# synthesizer-IF-Si4112-v1.net
KiCad netlist of a schematic drawn in EAGLE
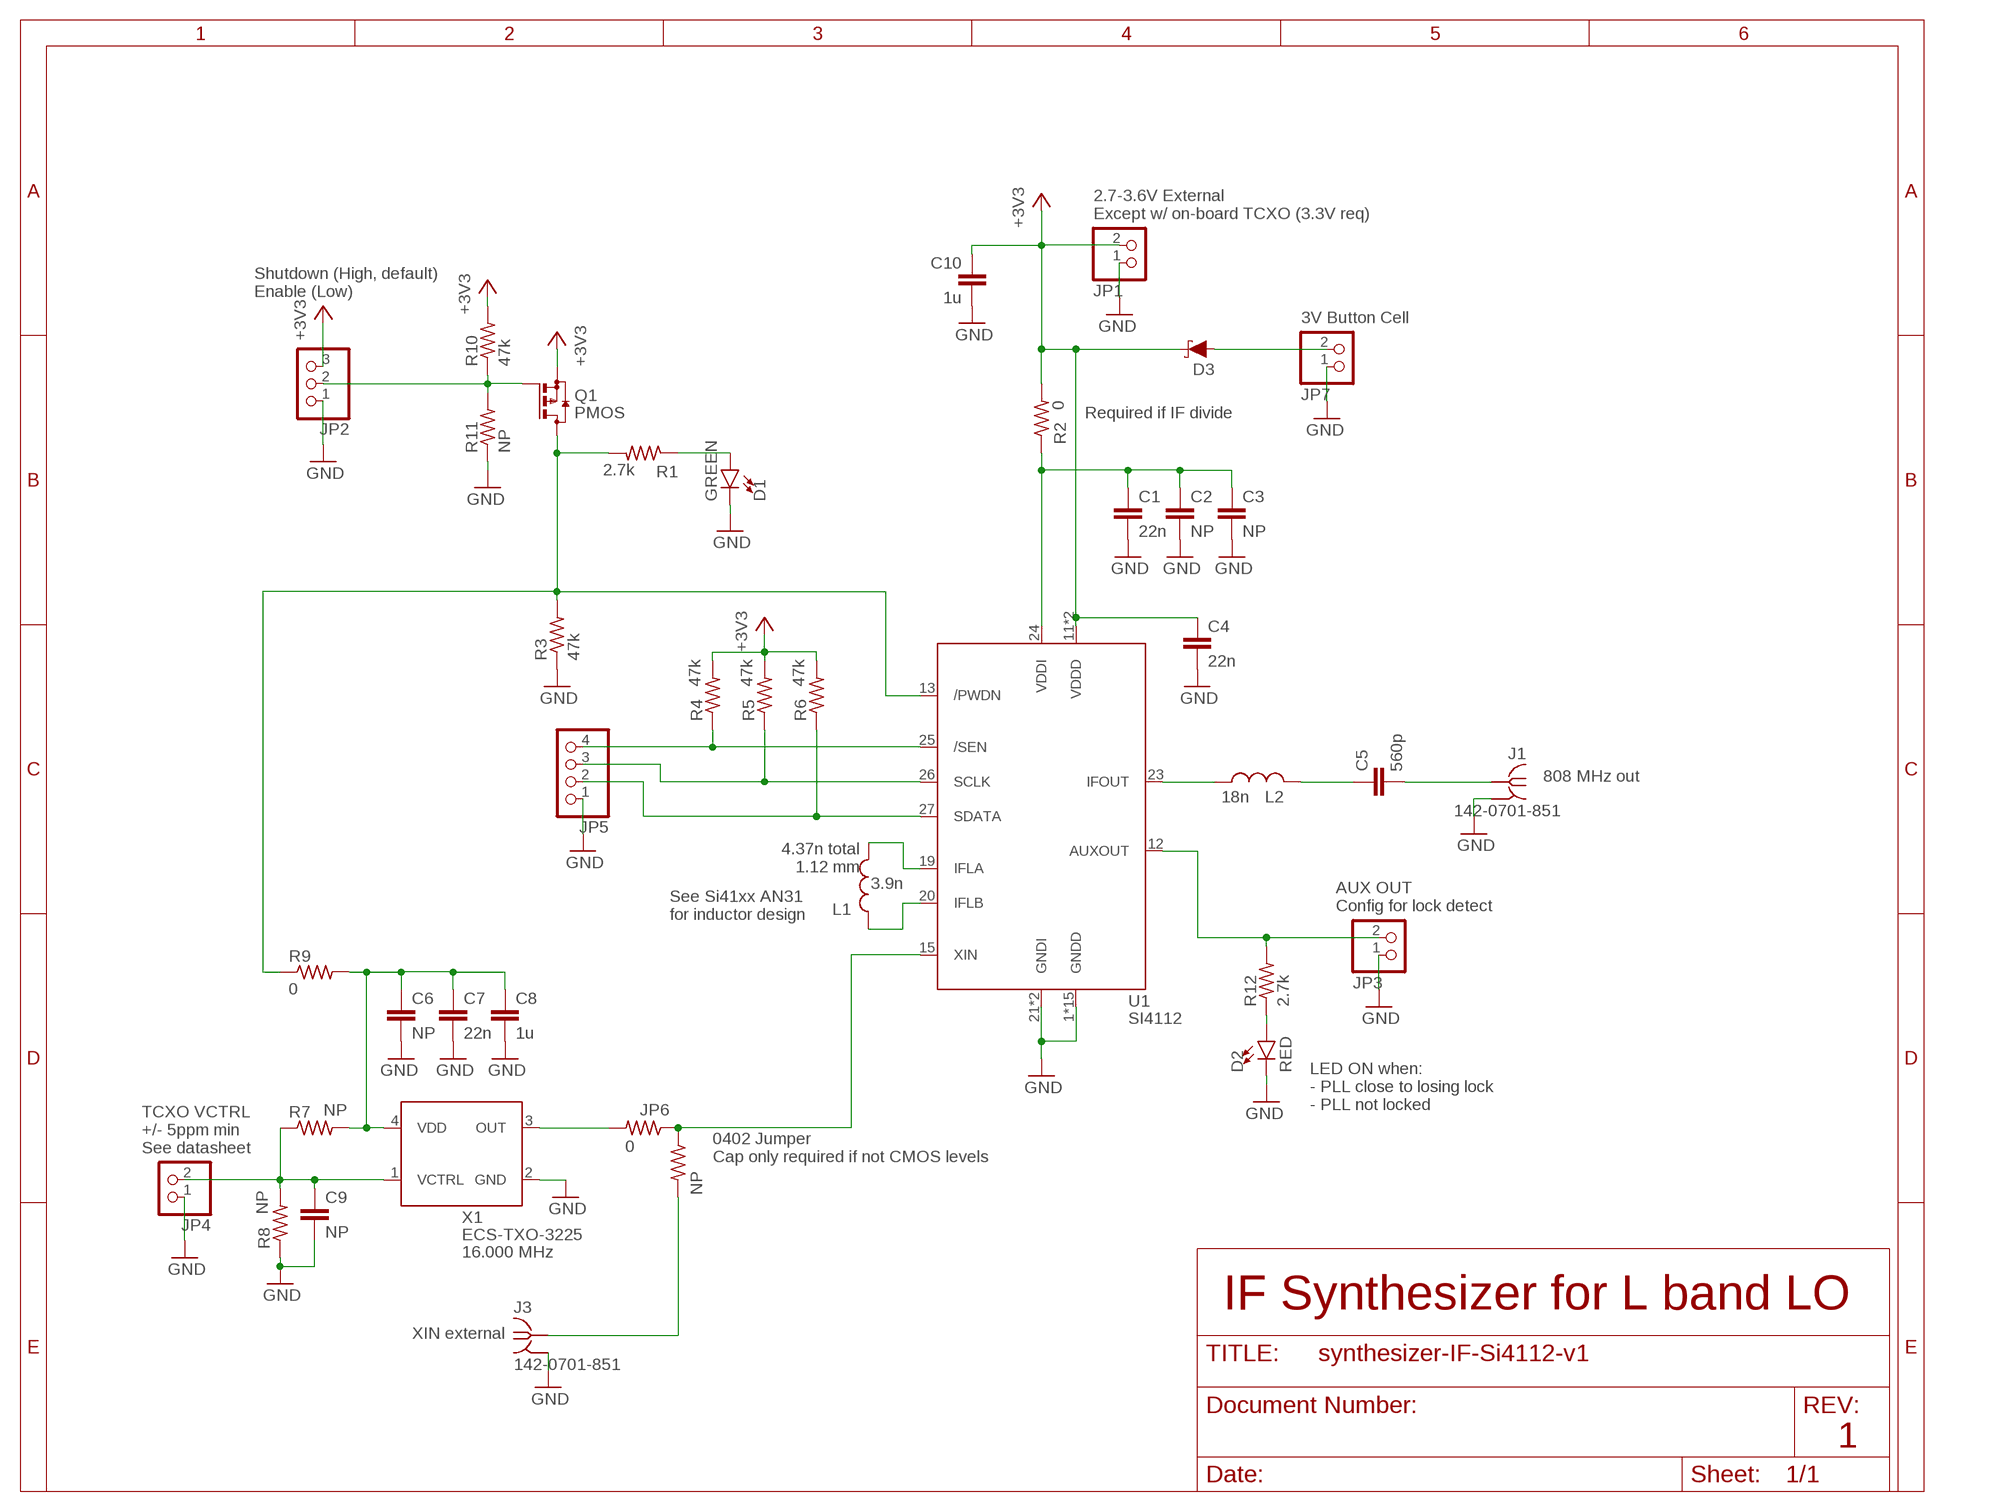
[diagram p0: schematic, sheet 1]

(export (version "E")
  (design (tool "Eeschema 10.0.6"))
  (components
    (comp (ref "C1")
      (value "22n")
      (footprint "eagle-import:.0603-B-NOSILK")
      (libsource (lib "eagle-import") (part "C-EU0603-B-NOSILK"))
    )
    (comp (ref "C2")
      (value "NP")
      (footprint "eagle-import:.0603-B-NOSILK")
      (libsource (lib "eagle-import") (part "C-EU0603-B-NOSILK"))
    )
    (comp (ref "C3")
      (value "NP")
      (footprint "eagle-import:.0603-B-NOSILK")
      (libsource (lib "eagle-import") (part "C-EU0603-B-NOSILK"))
    )
    (comp (ref "C4")
      (value "22n")
      (footprint "eagle-import:.0603-B-NOSILK")
      (libsource (lib "eagle-import") (part "C-EU0603-B-NOSILK"))
    )
    (comp (ref "C5")
      (value "560p")
      (footprint "eagle-import:.0402-B-NOSILK")
      (libsource (lib "eagle-import") (part "C-EU0402-B-NOSILK"))
    )
    (comp (ref "C6")
      (value "NP")
      (footprint "eagle-import:.0603-B-NOSILK")
      (libsource (lib "eagle-import") (part "C-EU0603-B-NOSILK"))
    )
    (comp (ref "C7")
      (value "22n")
      (footprint "eagle-import:.0603-B-NOSILK")
      (libsource (lib "eagle-import") (part "C-EU0603-B-NOSILK"))
    )
    (comp (ref "C8")
      (value "1u")
      (footprint "eagle-import:.0603-B-NOSILK")
      (libsource (lib "eagle-import") (part "C-EU0603-B-NOSILK"))
    )
    (comp (ref "C9")
      (value "NP")
      (footprint "eagle-import:.0603-B-NOSILK")
      (libsource (lib "eagle-import") (part "C-EU0603-B-NOSILK"))
    )
    (comp (ref "C10")
      (value "1u")
      (footprint "eagle-import:.0603-B-NOSILK")
      (libsource (lib "eagle-import") (part "C-EU0603-B-NOSILK"))
    )
    (comp (ref "D1")
      (value "GREEN")
      (footprint "eagle-import:LED-0603")
      (libsource (lib "eagle-import") (part "LED-GREEN0603"))
    )
    (comp (ref "D2")
      (value "RED")
      (footprint "eagle-import:LED-0603")
      (libsource (lib "eagle-import") (part "LED-GREEN0603"))
    )
    (comp (ref "D3")
      (value "120mA/40V/370mV")
      (footprint "eagle-import:SOD-523")
      (libsource (lib "eagle-import") (part "DIODE-SCHOTTKY-RB751S40"))
    )
    (comp (ref "J1")
      (value "142-0701-851")
      (footprint "eagle-import:142-0701-851")
      (libsource (lib "eagle-import") (part "142-0701-851"))
    )
    (comp (ref "J3")
      (value "142-0701-851")
      (footprint "eagle-import:142-0701-851")
      (libsource (lib "eagle-import") (part "142-0701-851"))
    )
    (comp (ref "JP1")
      (value "PINHD-1X2")
      (footprint "eagle-import:1X02")
      (libsource (lib "eagle-import") (part "PINHD-1X2"))
    )
    (comp (ref "JP2")
      (value "PINHD-1X3")
      (footprint "eagle-import:1X03")
      (libsource (lib "eagle-import") (part "PINHD-1X3"))
    )
    (comp (ref "JP3")
      (value "PINHD-1X2")
      (footprint "eagle-import:1X02")
      (libsource (lib "eagle-import") (part "PINHD-1X2"))
    )
    (comp (ref "JP4")
      (value "PINHD-1X2")
      (footprint "eagle-import:1X02")
      (libsource (lib "eagle-import") (part "PINHD-1X2"))
    )
    (comp (ref "JP5")
      (value "PINHD-1X4")
      (footprint "eagle-import:1X04")
      (libsource (lib "eagle-import") (part "PINHD-1X4"))
    )
    (comp (ref "JP6")
      (value "0")
      (footprint "eagle-import:.0402-B-NOSILK")
      (libsource (lib "eagle-import") (part "R-US_0402-B-NOSILK"))
    )
    (comp (ref "JP7")
      (value "PINHD-1X2")
      (footprint "eagle-import:1X02")
      (libsource (lib "eagle-import") (part "PINHD-1X2"))
    )
    (comp (ref "L1")
      (value "3.9n")
      (footprint "eagle-import:.0402-C-NOSILK")
      (libsource (lib "eagle-import") (part "L-US0402-C-NOSILK"))
    )
    (comp (ref "L2")
      (value "18n")
      (footprint "eagle-import:.0402-B-NOSILK")
      (libsource (lib "eagle-import") (part "L-US0402-B-NOSILK"))
    )
    (comp (ref "Q1")
      (value "PMOS")
      (footprint "eagle-import:SOT23")
      (libsource (lib "eagle-import") (part "BSS84"))
    )
    (comp (ref "R1")
      (value "2.7k")
      (footprint "eagle-import:.0603-B-NOSILK")
      (libsource (lib "eagle-import") (part "R-US_0603-B-NOSILK"))
    )
    (comp (ref "R2")
      (value "0")
      (footprint "eagle-import:.0603-B-NOSILK")
      (libsource (lib "eagle-import") (part "R-US_0603-B-NOSILK"))
    )
    (comp (ref "R3")
      (value "47k")
      (footprint "eagle-import:.0402-B-NOSILK")
      (libsource (lib "eagle-import") (part "R-US_0402-B-NOSILK"))
    )
    (comp (ref "R4")
      (value "47k")
      (footprint "eagle-import:.0402-B-NOSILK")
      (libsource (lib "eagle-import") (part "R-US_0402-B-NOSILK"))
    )
    (comp (ref "R5")
      (value "47k")
      (footprint "eagle-import:.0402-B-NOSILK")
      (libsource (lib "eagle-import") (part "R-US_0402-B-NOSILK"))
    )
    (comp (ref "R6")
      (value "47k")
      (footprint "eagle-import:.0402-B-NOSILK")
      (libsource (lib "eagle-import") (part "R-US_0402-B-NOSILK"))
    )
    (comp (ref "R7")
      (value "NP")
      (footprint "eagle-import:.0603-B-NOSILK")
      (libsource (lib "eagle-import") (part "R-US_0603-B-NOSILK"))
    )
    (comp (ref "R8")
      (value "NP")
      (footprint "eagle-import:.0603-B-NOSILK")
      (libsource (lib "eagle-import") (part "R-US_0603-B-NOSILK"))
    )
    (comp (ref "R9")
      (value "0")
      (footprint "eagle-import:.0603-B-NOSILK")
      (libsource (lib "eagle-import") (part "R-US_0603-B-NOSILK"))
    )
    (comp (ref "R10")
      (value "47k")
      (footprint "eagle-import:.0402-B-NOSILK")
      (libsource (lib "eagle-import") (part "R-US_0402-B-NOSILK"))
    )
    (comp (ref "R11")
      (value "NP")
      (footprint "eagle-import:.0402-B-NOSILK")
      (libsource (lib "eagle-import") (part "R-US_0402-B-NOSILK"))
    )
    (comp (ref "R12")
      (value "2.7k")
      (footprint "eagle-import:.0603-B-NOSILK")
      (libsource (lib "eagle-import") (part "R-US_0603-B-NOSILK"))
    )
    (comp (ref "R99")
      (value "NP")
      (footprint "eagle-import:.0402-B-NOSILK")
      (libsource (lib "eagle-import") (part "R-US_0402-B-NOSILK"))
    )
    (comp (ref "U1")
      (value "SI4112")
      (footprint "eagle-import:QFN28-5X5-WITH-CENTER-PAD")
      (libsource (lib "eagle-import") (part "SI4112"))
    )
    (comp (ref "X1")
      (value "ECS-TXO-3225")
      (footprint "eagle-import:3.2X2.5")
      (libsource (lib "eagle-import") (part "ECS-TXO-3225"))
    )
  )
  (nets
    (net (code "1") (name "+3V3") (class "Default")
      (node (ref "C10") (pin "1") (pinfunction "1_1") (pintype "passive"))
      (node (ref "C4") (pin "1") (pinfunction "1_1") (pintype "passive"))
      (node (ref "D3") (pin "C") (pinfunction "C_C") (pintype "passive"))
      (node (ref "JP1") (pin "2") (pinfunction "2_2") (pintype "passive"))
      (node (ref "JP2") (pin "3") (pinfunction "3_3") (pintype "passive"))
      (node (ref "Q1") (pin "2") (pinfunction "S_2") (pintype "passive"))
      (node (ref "R10") (pin "2") (pinfunction "2_2") (pintype "passive"))
      (node (ref "R2") (pin "2") (pinfunction "2_2") (pintype "passive"))
      (node (ref "R4") (pin "2") (pinfunction "2_2") (pintype "passive"))
      (node (ref "R5") (pin "2") (pinfunction "2_2") (pintype "passive"))
      (node (ref "R6") (pin "2") (pinfunction "2_2") (pintype "passive"))
      (node (ref "U1") (pin "11") (pinfunction "VDDD_11") (pintype "power_in"))
      (node (ref "U1") (pin "17") (pinfunction "VDDD_17") (pintype "power_in"))
    )
    (net (code "2") (name "GND") (class "Default")
      (node (ref "C1") (pin "2") (pinfunction "2_2") (pintype "passive"))
      (node (ref "C10") (pin "2") (pinfunction "2_2") (pintype "passive"))
      (node (ref "C2") (pin "2") (pinfunction "2_2") (pintype "passive"))
      (node (ref "C3") (pin "2") (pinfunction "2_2") (pintype "passive"))
      (node (ref "C4") (pin "2") (pinfunction "2_2") (pintype "passive"))
      (node (ref "C6") (pin "2") (pinfunction "2_2") (pintype "passive"))
      (node (ref "C7") (pin "2") (pinfunction "2_2") (pintype "passive"))
      (node (ref "C8") (pin "2") (pinfunction "2_2") (pintype "passive"))
      (node (ref "C9") (pin "2") (pinfunction "2_2") (pintype "passive"))
      (node (ref "D1") (pin "C") (pinfunction "C_C") (pintype "passive"))
      (node (ref "D2") (pin "C") (pinfunction "C_C") (pintype "passive"))
      (node (ref "J1") (pin "GND1") (pinfunction "GND_GND1") (pintype "bidirectional"))
      (node (ref "J1") (pin "GND2") (pinfunction "GND_GND2") (pintype "bidirectional"))
      (node (ref "J1") (pin "GND3") (pinfunction "GND_GND3") (pintype "bidirectional"))
      (node (ref "J1") (pin "GND4") (pinfunction "GND_GND4") (pintype "bidirectional"))
      (node (ref "J3") (pin "GND1") (pinfunction "GND_GND1") (pintype "bidirectional"))
      (node (ref "J3") (pin "GND2") (pinfunction "GND_GND2") (pintype "bidirectional"))
      (node (ref "J3") (pin "GND3") (pinfunction "GND_GND3") (pintype "bidirectional"))
      (node (ref "J3") (pin "GND4") (pinfunction "GND_GND4") (pintype "bidirectional"))
      (node (ref "JP1") (pin "1") (pinfunction "1_1") (pintype "passive"))
      (node (ref "JP2") (pin "1") (pinfunction "1_1") (pintype "passive"))
      (node (ref "JP3") (pin "1") (pinfunction "1_1") (pintype "passive"))
      (node (ref "JP4") (pin "1") (pinfunction "1_1") (pintype "passive"))
      (node (ref "JP5") (pin "1") (pinfunction "1_1") (pintype "passive"))
      (node (ref "JP7") (pin "1") (pinfunction "1_1") (pintype "passive"))
      (node (ref "R11") (pin "1") (pinfunction "1_1") (pintype "passive"))
      (node (ref "R3") (pin "1") (pinfunction "1_1") (pintype "passive"))
      (node (ref "R8") (pin "1") (pinfunction "1_1") (pintype "passive"))
      (node (ref "U1") (pin "1") (pinfunction "GNDD_1") (pintype "power_in"))
      (node (ref "U1") (pin "10") (pinfunction "GNDD_10") (pintype "power_in"))
      (node (ref "U1") (pin "14") (pinfunction "GNDD_14") (pintype "power_in"))
      (node (ref "U1") (pin "16") (pinfunction "GNDD_16") (pintype "power_in"))
      (node (ref "U1") (pin "18") (pinfunction "GNDD_18") (pintype "power_in"))
      (node (ref "U1") (pin "2") (pinfunction "GNDD_2") (pintype "power_in"))
      (node (ref "U1") (pin "21") (pinfunction "GNDI_21") (pintype "power_in"))
      (node (ref "U1") (pin "22") (pinfunction "GNDI_22") (pintype "power_in"))
      (node (ref "U1") (pin "28") (pinfunction "GNDD_28") (pintype "power_in"))
      (node (ref "U1") (pin "3") (pinfunction "GNDD_3") (pintype "power_in"))
      (node (ref "U1") (pin "4") (pinfunction "GNDD_4") (pintype "power_in"))
      (node (ref "U1") (pin "5") (pinfunction "GNDD_5") (pintype "power_in"))
      (node (ref "U1") (pin "6") (pinfunction "GNDD_6") (pintype "power_in"))
      (node (ref "U1") (pin "7") (pinfunction "GNDD_7") (pintype "power_in"))
      (node (ref "U1") (pin "8") (pinfunction "GNDD_8") (pintype "power_in"))
      (node (ref "U1") (pin "9") (pinfunction "GNDD_9") (pintype "power_in"))
      (node (ref "U1") (pin "PAD") (pinfunction "GNDD_PAD") (pintype "power_in"))
      (node (ref "X1") (pin "2") (pinfunction "GND_2") (pintype "power_in"))
    )
    (net (code "3") (name "Net-(C5-Pad1)") (class "Default")
      (node (ref "C5") (pin "1") (pinfunction "1_1") (pintype "passive"))
      (node (ref "L2") (pin "2") (pinfunction "2_2") (pintype "passive"))
    )
    (net (code "4") (name "Net-(D1-PadA)") (class "Default")
      (node (ref "D1") (pin "A") (pinfunction "A_A") (pintype "passive"))
      (node (ref "R1") (pin "1") (pinfunction "1_1") (pintype "passive"))
    )
    (net (code "5") (name "Net-(D2-PadA)") (class "Default")
      (node (ref "D2") (pin "A") (pinfunction "A_A") (pintype "passive"))
      (node (ref "R12") (pin "1") (pinfunction "1_1") (pintype "passive"))
    )
    (net (code "6") (name "Net-(D3-PadA)") (class "Default")
      (node (ref "D3") (pin "A") (pinfunction "A_A") (pintype "passive"))
      (node (ref "JP7") (pin "2") (pinfunction "2_2") (pintype "passive"))
    )
    (net (code "7") (name "Net-(J1-RF)") (class "Default")
      (node (ref "C5") (pin "2") (pinfunction "2_2") (pintype "passive"))
      (node (ref "J1") (pin "RF1") (pinfunction "RF_RF1") (pintype "bidirectional"))
    )
    (net (code "8") (name "Net-(J3-RF)") (class "Default")
      (node (ref "J3") (pin "RF1") (pinfunction "RF_RF1") (pintype "bidirectional"))
      (node (ref "R99") (pin "2") (pinfunction "2_2") (pintype "passive"))
    )
    (net (code "9") (name "Net-(Q1-D)") (class "Default")
      (node (ref "Q1") (pin "3") (pinfunction "D_3") (pintype "passive"))
      (node (ref "R1") (pin "2") (pinfunction "2_2") (pintype "passive"))
      (node (ref "R3") (pin "2") (pinfunction "2_2") (pintype "passive"))
      (node (ref "R9") (pin "1") (pinfunction "1_1") (pintype "passive"))
      (node (ref "U1") (pin "13") (pinfunction "/PWDN_13") (pintype "input"))
    )
    (net (code "10") (name "Net-(Q1-G)") (class "Default")
      (node (ref "JP2") (pin "2") (pinfunction "2_2") (pintype "passive"))
      (node (ref "Q1") (pin "1") (pinfunction "G_1") (pintype "passive"))
      (node (ref "R10") (pin "1") (pinfunction "1_1") (pintype "passive"))
      (node (ref "R11") (pin "2") (pinfunction "2_2") (pintype "passive"))
    )
    (net (code "11") (name "Net-(U1-AUXOUT)") (class "Default")
      (node (ref "JP3") (pin "2") (pinfunction "2_2") (pintype "passive"))
      (node (ref "R12") (pin "2") (pinfunction "2_2") (pintype "passive"))
      (node (ref "U1") (pin "12") (pinfunction "AUXOUT_12") (pintype "output"))
    )
    (net (code "12") (name "Net-(U1-IFLA)") (class "Default")
      (node (ref "L1") (pin "2") (pinfunction "2_2") (pintype "passive"))
      (node (ref "U1") (pin "19") (pinfunction "IFLA_19") (pintype "input"))
    )
    (net (code "13") (name "Net-(U1-IFLB)") (class "Default")
      (node (ref "L1") (pin "1") (pinfunction "1_1") (pintype "passive"))
      (node (ref "U1") (pin "20") (pinfunction "IFLB_20") (pintype "input"))
    )
    (net (code "14") (name "Net-(U1-IFOUT)") (class "Default")
      (node (ref "L2") (pin "1") (pinfunction "1_1") (pintype "passive"))
      (node (ref "U1") (pin "23") (pinfunction "IFOUT_23") (pintype "output"))
    )
    (net (code "15") (name "Net-(U1-SCLK)") (class "Default")
      (node (ref "JP5") (pin "3") (pinfunction "3_3") (pintype "passive"))
      (node (ref "R5") (pin "1") (pinfunction "1_1") (pintype "passive"))
      (node (ref "U1") (pin "26") (pinfunction "SCLK_26") (pintype "input"))
    )
    (net (code "16") (name "Net-(U1-SDATA)") (class "Default")
      (node (ref "JP5") (pin "2") (pinfunction "2_2") (pintype "passive"))
      (node (ref "R6") (pin "1") (pinfunction "1_1") (pintype "passive"))
      (node (ref "U1") (pin "27") (pinfunction "SDATA_27") (pintype "input"))
    )
    (net (code "17") (name "Net-(U1-VDDI)") (class "Default")
      (node (ref "C1") (pin "1") (pinfunction "1_1") (pintype "passive"))
      (node (ref "C2") (pin "1") (pinfunction "1_1") (pintype "passive"))
      (node (ref "C3") (pin "1") (pinfunction "1_1") (pintype "passive"))
      (node (ref "R2") (pin "1") (pinfunction "1_1") (pintype "passive"))
      (node (ref "U1") (pin "24") (pinfunction "VDDI_24") (pintype "power_in"))
    )
    (net (code "18") (name "Net-(U1-XIN)") (class "Default")
      (node (ref "JP6") (pin "1") (pinfunction "1_1") (pintype "passive"))
      (node (ref "R99") (pin "1") (pinfunction "1_1") (pintype "passive"))
      (node (ref "U1") (pin "15") (pinfunction "XIN_15") (pintype "input"))
    )
    (net (code "19") (name "Net-(U1-{slash}SEN)") (class "Default")
      (node (ref "JP5") (pin "4") (pinfunction "4_4") (pintype "passive"))
      (node (ref "R4") (pin "1") (pinfunction "1_1") (pintype "passive"))
      (node (ref "U1") (pin "25") (pinfunction "/SEN_25") (pintype "input"))
    )
    (net (code "20") (name "Net-(X1-OUT)") (class "Default")
      (node (ref "JP6") (pin "2") (pinfunction "2_2") (pintype "passive"))
      (node (ref "X1") (pin "3") (pinfunction "OUT_3") (pintype "output"))
    )
    (net (code "21") (name "Net-(X1-VCTRL)") (class "Default")
      (node (ref "C9") (pin "1") (pinfunction "1_1") (pintype "passive"))
      (node (ref "JP4") (pin "2") (pinfunction "2_2") (pintype "passive"))
      (node (ref "R7") (pin "1") (pinfunction "1_1") (pintype "passive"))
      (node (ref "R8") (pin "2") (pinfunction "2_2") (pintype "passive"))
      (node (ref "X1") (pin "1") (pinfunction "VCTRL_1") (pintype "input"))
    )
    (net (code "22") (name "Net-(X1-VDD)") (class "Default")
      (node (ref "C6") (pin "1") (pinfunction "1_1") (pintype "passive"))
      (node (ref "C7") (pin "1") (pinfunction "1_1") (pintype "passive"))
      (node (ref "C8") (pin "1") (pinfunction "1_1") (pintype "passive"))
      (node (ref "R7") (pin "2") (pinfunction "2_2") (pintype "passive"))
      (node (ref "R9") (pin "2") (pinfunction "2_2") (pintype "passive"))
      (node (ref "X1") (pin "4") (pinfunction "VDD_4") (pintype "power_in"))
    )
  )
)
